# DIO-SMA_Supply.net
KiCad netlist of a schematic drawn in Altium Designer
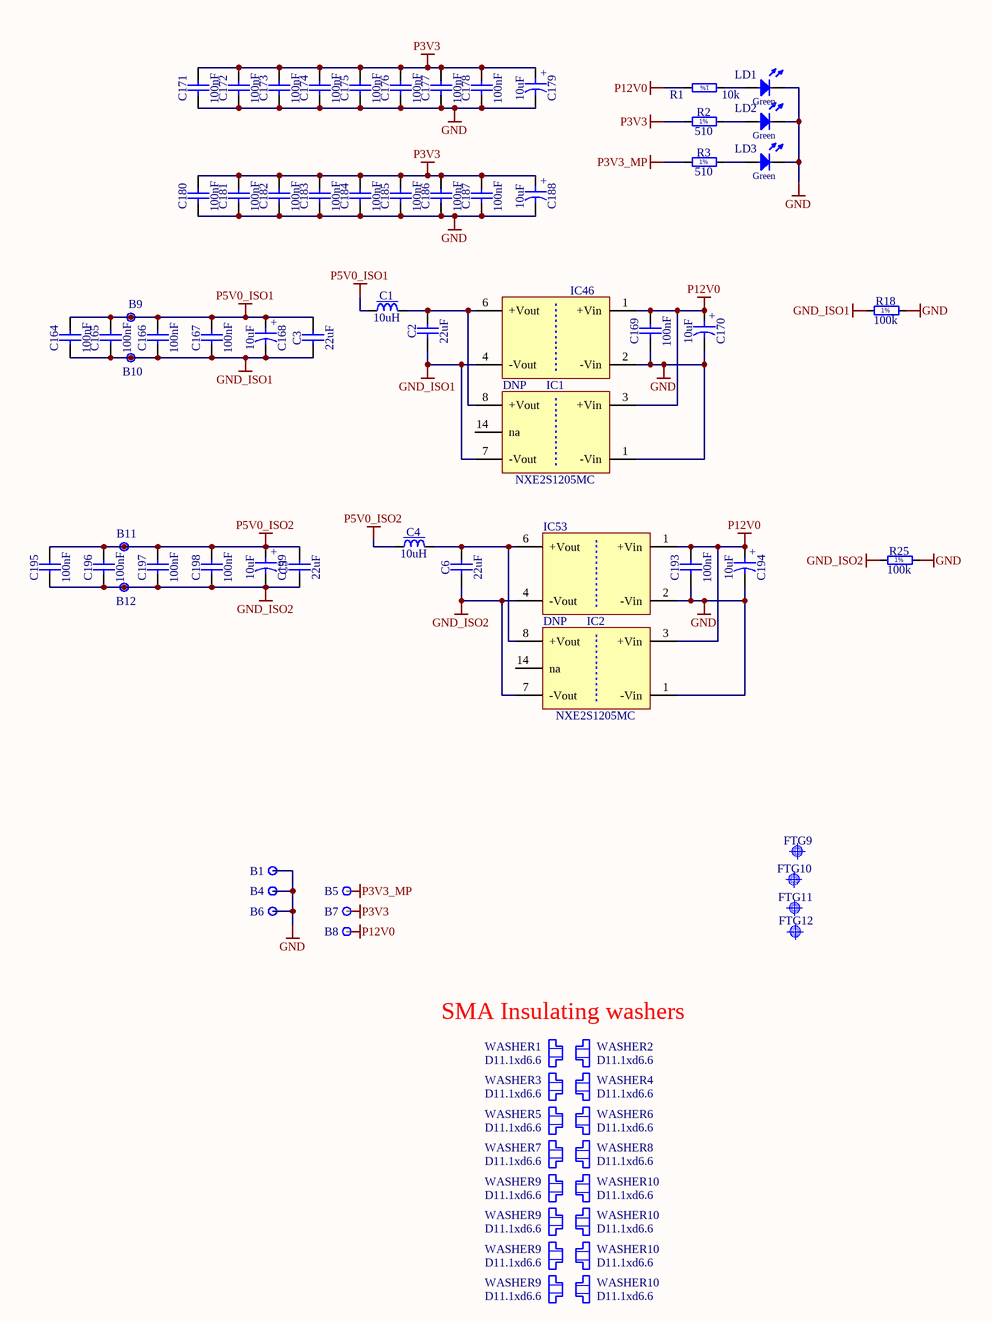
[diagram p0: DIO-SMA_Supply.SchDoc]

(export (version "E")
  (design (tool "Eeschema 10.0.6"))
  (components
    (comp (ref "B1")
      (value "Plated Hole")
      (footprint "c130h60")
      (description "Single Terminal Socket")
      (fields (field (name "PART NUMBER") "PLATED_HOLE0.6_PAD1.3") (field (name "AUTHOR") "CERN DEM MR"))
      (libsource (lib "Eletro-mechanical") (part "Single Terminal Socket"))
    )
    (comp (ref "B4")
      (value "Plated Hole")
      (footprint "c130h60")
      (description "Single Terminal Socket")
      (fields (field (name "PART NUMBER") "PLATED_HOLE0.6_PAD1.3") (field (name "AUTHOR") "CERN DEM MR"))
      (libsource (lib "Eletro-mechanical") (part "Single Terminal Socket"))
    )
    (comp (ref "B5")
      (value "Plated Hole")
      (footprint "c130h60")
      (description "Single Terminal Socket")
      (fields (field (name "PART NUMBER") "PLATED_HOLE0.6_PAD1.3") (field (name "AUTHOR") "CERN DEM MR"))
      (libsource (lib "Eletro-mechanical") (part "Single Terminal Socket"))
    )
    (comp (ref "B6")
      (value "Plated Hole")
      (footprint "c130h60")
      (description "Single Terminal Socket")
      (fields (field (name "PART NUMBER") "PLATED_HOLE0.6_PAD1.3") (field (name "AUTHOR") "CERN DEM MR"))
      (libsource (lib "Eletro-mechanical") (part "Single Terminal Socket"))
    )
    (comp (ref "B7")
      (value "Plated Hole")
      (footprint "c130h60")
      (description "Single Terminal Socket")
      (fields (field (name "PART NUMBER") "PLATED_HOLE0.6_PAD1.3") (field (name "AUTHOR") "CERN DEM MR"))
      (libsource (lib "Eletro-mechanical") (part "Single Terminal Socket"))
    )
    (comp (ref "B8")
      (value "Plated Hole")
      (footprint "c130h60")
      (description "Single Terminal Socket")
      (fields (field (name "PART NUMBER") "PLATED_HOLE0.6_PAD1.3") (field (name "AUTHOR") "CERN DEM MR"))
      (libsource (lib "Eletro-mechanical") (part "Single Terminal Socket"))
    )
    (comp (ref "B9")
      (value "Plated Hole")
      (footprint "c130h60")
      (description "Single Terminal Socket")
      (fields (field (name "PART NUMBER") "PLATED_HOLE0.6_PAD1.3") (field (name "AUTHOR") "CERN DEM MR"))
      (libsource (lib "Eletro-mechanical") (part "Single Terminal Socket"))
    )
    (comp (ref "B10")
      (value "Plated Hole")
      (footprint "c130h60")
      (description "Single Terminal Socket")
      (fields (field (name "PART NUMBER") "PLATED_HOLE0.6_PAD1.3") (field (name "AUTHOR") "CERN DEM MR"))
      (libsource (lib "Eletro-mechanical") (part "Single Terminal Socket"))
    )
    (comp (ref "B11")
      (value "Plated Hole")
      (footprint "c130h60")
      (description "Single Terminal Socket")
      (fields (field (name "PART NUMBER") "PLATED_HOLE0.6_PAD1.3") (field (name "AUTHOR") "CERN DEM MR"))
      (libsource (lib "Eletro-mechanical") (part "Single Terminal Socket"))
    )
    (comp (ref "B12")
      (value "Plated Hole")
      (footprint "c130h60")
      (description "Single Terminal Socket")
      (fields (field (name "PART NUMBER") "PLATED_HOLE0.6_PAD1.3") (field (name "AUTHOR") "CERN DEM MR"))
      (libsource (lib "Eletro-mechanical") (part "Single Terminal Socket"))
    )
    (comp (ref "C1")
      (value "10uH")
      (footprint "IND_MURATA-PS_8400")
      (description "Inductor With Core")
      (fields
        (field (name "PART NUMBER") "IND_10UH_10%_MURATA-PS_8400")
        (field (name "POWER") "950mA")
        (field (name "AUTHOR") "CERN DEM JLC")
      )
      (libsource (lib "Inductors & Transformers") (part "Inductor With Magnetic core"))
    )
    (comp (ref "C2")
      (value "22uF")
      (footprint "CAPC2012X135N")
      (description "Non-polarised capacitor")
      (fields
        (field (name "PART NUMBER") "CC0805_22UF_16V_10%_X5R")
        (field (name "VOLTAGE") "16V")
        (field (name "AUTHOR") "CERN DEM JLC")
      )
      (libsource (lib "Capacitors") (part "Capacitor - non polarized"))
    )
    (comp (ref "C3")
      (value "22uF")
      (footprint "CAPC2012X135N")
      (description "Non-polarised capacitor")
      (fields
        (field (name "PART NUMBER") "CC0805_22UF_16V_10%_X5R")
        (field (name "VOLTAGE") "16V")
        (field (name "AUTHOR") "CERN DEM JLC")
      )
      (libsource (lib "Capacitors") (part "Capacitor - non polarized"))
    )
    (comp (ref "C4")
      (value "10uH")
      (footprint "IND_MURATA-PS_8400")
      (description "Inductor With Core")
      (fields
        (field (name "PART NUMBER") "IND_10UH_10%_MURATA-PS_8400")
        (field (name "POWER") "950mA")
        (field (name "AUTHOR") "CERN DEM JLC")
      )
      (libsource (lib "Inductors & Transformers") (part "Inductor With Magnetic core"))
    )
    (comp (ref "C5")
      (value "22uF")
      (footprint "CAPC2012X135N")
      (description "Non-polarised capacitor")
      (fields
        (field (name "PART NUMBER") "CC0805_22UF_16V_10%_X5R")
        (field (name "VOLTAGE") "16V")
        (field (name "AUTHOR") "CERN DEM JLC")
      )
      (libsource (lib "Capacitors") (part "Capacitor - non polarized"))
    )
    (comp (ref "C6")
      (value "22uF")
      (footprint "CAPC2012X135N")
      (description "Non-polarised capacitor")
      (fields
        (field (name "PART NUMBER") "CC0805_22UF_16V_10%_X5R")
        (field (name "VOLTAGE") "16V")
        (field (name "AUTHOR") "CERN DEM JLC")
      )
      (libsource (lib "Capacitors") (part "Capacitor - non polarized"))
    )
    (comp (ref "C164")
      (value "100nF")
      (footprint "CAPC1005X55N")
      (description "Non-polarised capacitor")
      (fields
        (field (name "PART NUMBER") "CC0402_100NF_16V_10%_X5R")
        (field (name "VOLTAGE") "16V")
        (field (name "AUTHOR") "CERN DEM JLC")
      )
      (libsource (lib "Capacitors") (part "Capacitor - non polarized"))
    )
    (comp (ref "C165")
      (value "100nF")
      (footprint "CAPC1005X55N")
      (description "Non-polarised capacitor")
      (fields
        (field (name "PART NUMBER") "CC0402_100NF_16V_10%_X5R")
        (field (name "VOLTAGE") "16V")
        (field (name "AUTHOR") "CERN DEM JLC")
      )
      (libsource (lib "Capacitors") (part "Capacitor - non polarized"))
    )
    (comp (ref "C166")
      (value "100nF")
      (footprint "CAPC1005X55N")
      (description "Non-polarised capacitor")
      (fields
        (field (name "PART NUMBER") "CC0402_100NF_16V_10%_X5R")
        (field (name "VOLTAGE") "16V")
        (field (name "AUTHOR") "CERN DEM JLC")
      )
      (libsource (lib "Capacitors") (part "Capacitor - non polarized"))
    )
    (comp (ref "C167")
      (value "100nF")
      (footprint "CAPC1005X55N")
      (description "Non-polarised capacitor")
      (fields
        (field (name "PART NUMBER") "CC0402_100NF_16V_10%_X5R")
        (field (name "VOLTAGE") "16V")
        (field (name "AUTHOR") "CERN DEM JLC")
      )
      (libsource (lib "Capacitors") (part "Capacitor - non polarized"))
    )
    (comp (ref "C168")
      (value "10uF")
      (footprint "CAPAE430X540N")
      (description "Polarised capacitor")
      (fields
        (field (name "PART NUMBER") "CAE430-540_10UF_16V_20%")
        (field (name "VOLTAGE") "16V")
        (field (name "AUTHOR") "CERN DEM JLC")
      )
      (libsource (lib "Capacitors") (part "Capacitor - polarized"))
    )
    (comp (ref "C169")
      (value "100nF")
      (footprint "CAPC1005X55N")
      (description "Non-polarised capacitor")
      (fields
        (field (name "PART NUMBER") "CC0402_100NF_16V_10%_X5R")
        (field (name "VOLTAGE") "16V")
        (field (name "AUTHOR") "CERN DEM JLC")
      )
      (libsource (lib "Capacitors") (part "Capacitor - non polarized"))
    )
    (comp (ref "C170")
      (value "10uF")
      (footprint "CAPAE430X540N")
      (description "Polarised capacitor")
      (fields
        (field (name "PART NUMBER") "CAE430-540_10UF_16V_20%")
        (field (name "VOLTAGE") "16V")
        (field (name "AUTHOR") "CERN DEM JLC")
      )
      (libsource (lib "Capacitors") (part "Capacitor - polarized"))
    )
    (comp (ref "C171")
      (value "100nF")
      (footprint "CAPC1005X55N")
      (description "Non-polarised capacitor")
      (fields
        (field (name "PART NUMBER") "CC0402_100NF_16V_10%_X5R")
        (field (name "VOLTAGE") "16V")
        (field (name "AUTHOR") "CERN DEM JLC")
      )
      (libsource (lib "Capacitors") (part "Capacitor - non polarized"))
    )
    (comp (ref "C172")
      (value "100nF")
      (footprint "CAPC1005X55N")
      (description "Non-polarised capacitor")
      (fields
        (field (name "PART NUMBER") "CC0402_100NF_16V_10%_X5R")
        (field (name "VOLTAGE") "16V")
        (field (name "AUTHOR") "CERN DEM JLC")
      )
      (libsource (lib "Capacitors") (part "Capacitor - non polarized"))
    )
    (comp (ref "C173")
      (value "100nF")
      (footprint "CAPC1005X55N")
      (description "Non-polarised capacitor")
      (fields
        (field (name "PART NUMBER") "CC0402_100NF_16V_10%_X5R")
        (field (name "VOLTAGE") "16V")
        (field (name "AUTHOR") "CERN DEM JLC")
      )
      (libsource (lib "Capacitors") (part "Capacitor - non polarized"))
    )
    (comp (ref "C174")
      (value "100nF")
      (footprint "CAPC1005X55N")
      (description "Non-polarised capacitor")
      (fields
        (field (name "PART NUMBER") "CC0402_100NF_16V_10%_X5R")
        (field (name "VOLTAGE") "16V")
        (field (name "AUTHOR") "CERN DEM JLC")
      )
      (libsource (lib "Capacitors") (part "Capacitor - non polarized"))
    )
    (comp (ref "C175")
      (value "100nF")
      (footprint "CAPC1005X55N")
      (description "Non-polarised capacitor")
      (fields
        (field (name "PART NUMBER") "CC0402_100NF_16V_10%_X5R")
        (field (name "VOLTAGE") "16V")
        (field (name "AUTHOR") "CERN DEM JLC")
      )
      (libsource (lib "Capacitors") (part "Capacitor - non polarized"))
    )
    (comp (ref "C176")
      (value "100nF")
      (footprint "CAPC1005X55N")
      (description "Non-polarised capacitor")
      (fields
        (field (name "PART NUMBER") "CC0402_100NF_16V_10%_X5R")
        (field (name "VOLTAGE") "16V")
        (field (name "AUTHOR") "CERN DEM JLC")
      )
      (libsource (lib "Capacitors") (part "Capacitor - non polarized"))
    )
    (comp (ref "C177")
      (value "100nF")
      (footprint "CAPC1005X55N")
      (description "Non-polarised capacitor")
      (fields
        (field (name "PART NUMBER") "CC0402_100NF_16V_10%_X5R")
        (field (name "VOLTAGE") "16V")
        (field (name "AUTHOR") "CERN DEM JLC")
      )
      (libsource (lib "Capacitors") (part "Capacitor - non polarized"))
    )
    (comp (ref "C178")
      (value "100nF")
      (footprint "CAPC1005X55N")
      (description "Non-polarised capacitor")
      (fields
        (field (name "PART NUMBER") "CC0402_100NF_16V_10%_X5R")
        (field (name "VOLTAGE") "16V")
        (field (name "AUTHOR") "CERN DEM JLC")
      )
      (libsource (lib "Capacitors") (part "Capacitor - non polarized"))
    )
    (comp (ref "C179")
      (value "10uF")
      (footprint "CAPAE430X540N")
      (description "Polarised capacitor")
      (fields
        (field (name "PART NUMBER") "CAE430-540_10UF_16V_20%")
        (field (name "VOLTAGE") "16V")
        (field (name "AUTHOR") "CERN DEM JLC")
      )
      (libsource (lib "Capacitors") (part "Capacitor - polarized"))
    )
    (comp (ref "C180")
      (value "100nF")
      (footprint "CAPC1005X55N")
      (description "Non-polarised capacitor")
      (fields
        (field (name "PART NUMBER") "CC0402_100NF_16V_10%_X5R")
        (field (name "VOLTAGE") "16V")
        (field (name "AUTHOR") "CERN DEM JLC")
      )
      (libsource (lib "Capacitors") (part "Capacitor - non polarized"))
    )
    (comp (ref "C181")
      (value "100nF")
      (footprint "CAPC1005X55N")
      (description "Non-polarised capacitor")
      (fields
        (field (name "PART NUMBER") "CC0402_100NF_16V_10%_X5R")
        (field (name "VOLTAGE") "16V")
        (field (name "AUTHOR") "CERN DEM JLC")
      )
      (libsource (lib "Capacitors") (part "Capacitor - non polarized"))
    )
    (comp (ref "C182")
      (value "100nF")
      (footprint "CAPC1005X55N")
      (description "Non-polarised capacitor")
      (fields
        (field (name "PART NUMBER") "CC0402_100NF_16V_10%_X5R")
        (field (name "VOLTAGE") "16V")
        (field (name "AUTHOR") "CERN DEM JLC")
      )
      (libsource (lib "Capacitors") (part "Capacitor - non polarized"))
    )
    (comp (ref "C183")
      (value "100nF")
      (footprint "CAPC1005X55N")
      (description "Non-polarised capacitor")
      (fields
        (field (name "PART NUMBER") "CC0402_100NF_16V_10%_X5R")
        (field (name "VOLTAGE") "16V")
        (field (name "AUTHOR") "CERN DEM JLC")
      )
      (libsource (lib "Capacitors") (part "Capacitor - non polarized"))
    )
    (comp (ref "C184")
      (value "100nF")
      (footprint "CAPC1005X55N")
      (description "Non-polarised capacitor")
      (fields
        (field (name "PART NUMBER") "CC0402_100NF_16V_10%_X5R")
        (field (name "VOLTAGE") "16V")
        (field (name "AUTHOR") "CERN DEM JLC")
      )
      (libsource (lib "Capacitors") (part "Capacitor - non polarized"))
    )
    (comp (ref "C185")
      (value "100nF")
      (footprint "CAPC1005X55N")
      (description "Non-polarised capacitor")
      (fields
        (field (name "PART NUMBER") "CC0402_100NF_16V_10%_X5R")
        (field (name "VOLTAGE") "16V")
        (field (name "AUTHOR") "CERN DEM JLC")
      )
      (libsource (lib "Capacitors") (part "Capacitor - non polarized"))
    )
    (comp (ref "C186")
      (value "100nF")
      (footprint "CAPC1005X55N")
      (description "Non-polarised capacitor")
      (fields
        (field (name "PART NUMBER") "CC0402_100NF_16V_10%_X5R")
        (field (name "VOLTAGE") "16V")
        (field (name "AUTHOR") "CERN DEM JLC")
      )
      (libsource (lib "Capacitors") (part "Capacitor - non polarized"))
    )
    (comp (ref "C187")
      (value "100nF")
      (footprint "CAPC1005X55N")
      (description "Non-polarised capacitor")
      (fields
        (field (name "PART NUMBER") "CC0402_100NF_16V_10%_X5R")
        (field (name "VOLTAGE") "16V")
        (field (name "AUTHOR") "CERN DEM JLC")
      )
      (libsource (lib "Capacitors") (part "Capacitor - non polarized"))
    )
    (comp (ref "C188")
      (value "10uF")
      (footprint "CAPAE430X540N")
      (description "Polarised capacitor")
      (fields
        (field (name "PART NUMBER") "CAE430-540_10UF_16V_20%")
        (field (name "VOLTAGE") "16V")
        (field (name "AUTHOR") "CERN DEM JLC")
      )
      (libsource (lib "Capacitors") (part "Capacitor - polarized"))
    )
    (comp (ref "C193")
      (value "100nF")
      (footprint "CAPC1005X55N")
      (description "Non-polarised capacitor")
      (fields
        (field (name "PART NUMBER") "CC0402_100NF_16V_10%_X5R")
        (field (name "VOLTAGE") "16V")
        (field (name "AUTHOR") "CERN DEM JLC")
      )
      (libsource (lib "Capacitors") (part "Capacitor - non polarized"))
    )
    (comp (ref "C194")
      (value "10uF")
      (footprint "CAPAE430X540N")
      (description "Polarised capacitor")
      (fields
        (field (name "PART NUMBER") "CAE430-540_10UF_16V_20%")
        (field (name "VOLTAGE") "16V")
        (field (name "AUTHOR") "CERN DEM JLC")
      )
      (libsource (lib "Capacitors") (part "Capacitor - polarized"))
    )
    (comp (ref "C195")
      (value "100nF")
      (footprint "CAPC1005X55N")
      (description "Non-polarised capacitor")
      (fields
        (field (name "PART NUMBER") "CC0402_100NF_16V_10%_X5R")
        (field (name "VOLTAGE") "16V")
        (field (name "AUTHOR") "CERN DEM JLC")
      )
      (libsource (lib "Capacitors") (part "Capacitor - non polarized"))
    )
    (comp (ref "C196")
      (value "100nF")
      (footprint "CAPC1005X55N")
      (description "Non-polarised capacitor")
      (fields
        (field (name "PART NUMBER") "CC0402_100NF_16V_10%_X5R")
        (field (name "VOLTAGE") "16V")
        (field (name "AUTHOR") "CERN DEM JLC")
      )
      (libsource (lib "Capacitors") (part "Capacitor - non polarized"))
    )
    (comp (ref "C197")
      (value "100nF")
      (footprint "CAPC1005X55N")
      (description "Non-polarised capacitor")
      (fields
        (field (name "PART NUMBER") "CC0402_100NF_16V_10%_X5R")
        (field (name "VOLTAGE") "16V")
        (field (name "AUTHOR") "CERN DEM JLC")
      )
      (libsource (lib "Capacitors") (part "Capacitor - non polarized"))
    )
    (comp (ref "C198")
      (value "100nF")
      (footprint "CAPC1005X55N")
      (description "Non-polarised capacitor")
      (fields
        (field (name "PART NUMBER") "CC0402_100NF_16V_10%_X5R")
        (field (name "VOLTAGE") "16V")
        (field (name "AUTHOR") "CERN DEM JLC")
      )
      (libsource (lib "Capacitors") (part "Capacitor - non polarized"))
    )
    (comp (ref "C199")
      (value "10uF")
      (footprint "CAPAE430X540N")
      (description "Polarised capacitor")
      (fields
        (field (name "PART NUMBER") "CAE430-540_10UF_16V_20%")
        (field (name "VOLTAGE") "16V")
        (field (name "AUTHOR") "CERN DEM JLC")
      )
      (libsource (lib "Capacitors") (part "Capacitor - polarized"))
    )
    (comp (ref "FTG9")
      (value "Use only in PCB")
      (footprint "FIDUCIAL_TOP_C100-200")
      (description "Fiducial Target")
      (fields (field (name "PART NUMBER") "FIDUCIAL_TARGET_C100-200") (field (name "AUTHOR") "CERN DEM JLC"))
      (libsource (lib "Eletro-mechanical") (part "Fiducial Target"))
    )
    (comp (ref "FTG10")
      (value "Use only in PCB")
      (footprint "FIDUCIAL_TOP_S100-200")
      (description "Fiducial Target")
      (fields (field (name "PART NUMBER") "FIDUCIAL_TARGET_S100-200") (field (name "AUTHOR") "CERN DEM JLC"))
      (libsource (lib "Eletro-mechanical") (part "Fiducial Target"))
    )
    (comp (ref "FTG11")
      (value "Use only in PCB")
      (footprint "FIDUCIAL_TOP_S200-400")
      (description "Fiducial Target")
      (fields (field (name "PART NUMBER") "FIDUCIAL_TARGET_S200-400") (field (name "AUTHOR") "CERN DEM JLC"))
      (libsource (lib "Eletro-mechanical") (part "Fiducial Target"))
    )
    (comp (ref "FTG12")
      (value "Use only in PCB")
      (footprint "FIDUCIAL_TOP_S100-200")
      (description "Fiducial Target")
      (fields (field (name "PART NUMBER") "FIDUCIAL_TARGET_S100-200") (field (name "AUTHOR") "CERN DEM JLC"))
      (libsource (lib "Eletro-mechanical") (part "Fiducial Target"))
    )
    (comp (ref "IC1")
      (value "NXE2S1205MC")
      (footprint "DCDC_MURATA_NXE2")
      (description "MURATA, NXE2 Serie, Dual Output DCDC Converter")
      (fields (field (name "MANUFACTURER") "MURATA POWER SOLUTIONS") (field (name "AUTHOR") "CERN DEM MR"))
      (libsource (lib "LIBRARY_SCH") (part "DCDC_MURATA_NXE2S1205MC"))
    )
    (comp (ref "IC2")
      (value "NXE2S1205MC")
      (footprint "DCDC_MURATA_NXE2")
      (description "MURATA, NXE2 Serie, Dual Output DCDC Converter")
      (fields (field (name "MANUFACTURER") "MURATA POWER SOLUTIONS") (field (name "AUTHOR") "CERN DEM MR"))
      (libsource (lib "LIBRARY_SCH") (part "DCDC_MURATA_NXE2S1205MC"))
    )
    (comp (ref "IC46")
      (value "DNP")
      (footprint "DCDC_TRACO_TMA")
      (description "1 W Watt, 10.8-13.2VDCVin, 5 V@0.2 A")
      (fields
        (field (name "PART NUMBER") "TMA 1205S")
        (field (name "MANUFACTURER") "TRACO POWER")
        (field (name "AUTHOR") "GK")
      )
      (libsource (lib "LIBRARY_SCH") (part "DC/DC_TRACO_TMA1205S"))
    )
    (comp (ref "IC53")
      (value "DNP")
      (footprint "DCDC_TRACO_TMA")
      (description "1 W Watt, 10.8-13.2VDCVin, 5 V@0.2 A")
      (fields
        (field (name "PART NUMBER") "TMA 1205S")
        (field (name "MANUFACTURER") "TRACO POWER")
        (field (name "AUTHOR") "GK")
      )
      (libsource (lib "LIBRARY_SCH") (part "DC/DC_TRACO_TMA1205S"))
    )
    (comp (ref "LD1")
      (value "Green")
      (footprint "LED_KINGBRIGHT_KPH-1608CGCK")
      (description "LED Green 1C 2A")
      (fields
        (field (name "PART NUMBER") "LED_KINGBRIGHT_KPH-1608CGCK")
        (field (name "MANUFACTURER") "KINGBRIGHT")
        (field (name "AUTHOR") "CERN DEM JLC")
      )
      (libsource (lib "ICs And Semiconductors") (part "LED Green 1C 2A"))
    )
    (comp (ref "LD2")
      (value "Green")
      (footprint "LED_KINGBRIGHT_KPH-1608CGCK")
      (description "LED Green 1C 2A")
      (fields
        (field (name "PART NUMBER") "LED_KINGBRIGHT_KPH-1608CGCK")
        (field (name "MANUFACTURER") "KINGBRIGHT")
        (field (name "AUTHOR") "CERN DEM JLC")
      )
      (libsource (lib "ICs And Semiconductors") (part "LED Green 1C 2A"))
    )
    (comp (ref "LD3")
      (value "Green")
      (footprint "LED_KINGBRIGHT_KPH-1608CGCK")
      (description "LED Green 1C 2A")
      (fields
        (field (name "PART NUMBER") "LED_KINGBRIGHT_KPH-1608CGCK")
        (field (name "MANUFACTURER") "KINGBRIGHT")
        (field (name "AUTHOR") "CERN DEM JLC")
      )
      (libsource (lib "ICs And Semiconductors") (part "LED Green 1C 2A"))
    )
    (comp (ref "R1")
      (value "10k")
      (footprint "RESC1005X40N")
      (description "Resistor - 1%")
      (fields
        (field (name "PART NUMBER") "R0402_10K_1%_0.0625W_100PPM")
        (field (name "POWER") "0.0625W")
        (field (name "AUTHOR") "CERN DEM JLC")
      )
      (libsource (lib "Resistors") (part "Resistor - 1%"))
    )
    (comp (ref "R2")
      (value "510")
      (footprint "RESC1005X40N")
      (description "Resistor - 1%")
      (fields
        (field (name "PART NUMBER") "R0402_510R_1%_0.0625W_100PPM")
        (field (name "POWER") "0.0625W")
        (field (name "AUTHOR") "CERN DEM JLC")
      )
      (libsource (lib "Resistors") (part "Resistor - 1%"))
    )
    (comp (ref "R3")
      (value "510")
      (footprint "RESC1005X40N")
      (description "Resistor - 1%")
      (fields
        (field (name "PART NUMBER") "R0402_510R_1%_0.0625W_100PPM")
        (field (name "POWER") "0.0625W")
        (field (name "AUTHOR") "CERN DEM JLC")
      )
      (libsource (lib "Resistors") (part "Resistor - 1%"))
    )
    (comp (ref "R18")
      (value "100k")
      (footprint "RESC2012X60N")
      (description "Resistor - 1%")
      (fields
        (field (name "PART NUMBER") "R0805_100K_1%_0.125W_100PPM")
        (field (name "POWER") "0.125W")
        (field (name "AUTHOR") "CERN DEM JLC")
      )
      (libsource (lib "Resistors") (part "Resistor - 1%"))
    )
    (comp (ref "R25")
      (value "100k")
      (footprint "RESC2012X60N")
      (description "Resistor - 1%")
      (fields
        (field (name "PART NUMBER") "R0805_100K_1%_0.125W_100PPM")
        (field (name "POWER") "0.125W")
        (field (name "AUTHOR") "CERN DEM JLC")
      )
      (libsource (lib "Resistors") (part "Resistor - 1%"))
    )
    (comp (ref "WASHER1")
      (value "D11.1xd6.6")
      (footprint "Keystone_7687")
      (description "SMA_Shoulder Washer")
      (fields
        (field (name "PART NUMBER") "Keystone 7687")
        (field (name "MANUFACTURER") "Keystone")
        (field (name "AUTHOR") "GK")
      )
      (libsource (lib "LIBRARY_SCH") (part "Keystone_7687"))
    )
    (comp (ref "WASHER2")
      (value "D11.1xd6.6")
      (footprint "Keystone_7687")
      (description "SMA_Shoulder Washer")
      (fields
        (field (name "PART NUMBER") "Keystone 7687")
        (field (name "MANUFACTURER") "Keystone")
        (field (name "AUTHOR") "GK")
      )
      (libsource (lib "LIBRARY_SCH") (part "Keystone_7687"))
    )
    (comp (ref "WASHER3")
      (value "D11.1xd6.6")
      (footprint "Keystone_7687")
      (description "SMA_Shoulder Washer")
      (fields
        (field (name "PART NUMBER") "Keystone 7687")
        (field (name "MANUFACTURER") "Keystone")
        (field (name "AUTHOR") "GK")
      )
      (libsource (lib "LIBRARY_SCH") (part "Keystone_7687"))
    )
    (comp (ref "WASHER4")
      (value "D11.1xd6.6")
      (footprint "Keystone_7687")
      (description "SMA_Shoulder Washer")
      (fields
        (field (name "PART NUMBER") "Keystone 7687")
        (field (name "MANUFACTURER") "Keystone")
        (field (name "AUTHOR") "GK")
      )
      (libsource (lib "LIBRARY_SCH") (part "Keystone_7687"))
    )
    (comp (ref "WASHER5")
      (value "D11.1xd6.6")
      (footprint "Keystone_7687")
      (description "SMA_Shoulder Washer")
      (fields
        (field (name "PART NUMBER") "Keystone 7687")
        (field (name "MANUFACTURER") "Keystone")
        (field (name "AUTHOR") "GK")
      )
      (libsource (lib "LIBRARY_SCH") (part "Keystone_7687"))
    )
    (comp (ref "WASHER6")
      (value "D11.1xd6.6")
      (footprint "Keystone_7687")
      (description "SMA_Shoulder Washer")
      (fields
        (field (name "PART NUMBER") "Keystone 7687")
        (field (name "MANUFACTURER") "Keystone")
        (field (name "AUTHOR") "GK")
      )
      (libsource (lib "LIBRARY_SCH") (part "Keystone_7687"))
    )
    (comp (ref "WASHER7")
      (value "D11.1xd6.6")
      (footprint "Keystone_7687")
      (description "SMA_Shoulder Washer")
      (fields
        (field (name "PART NUMBER") "Keystone 7687")
        (field (name "MANUFACTURER") "Keystone")
        (field (name "AUTHOR") "GK")
      )
      (libsource (lib "LIBRARY_SCH") (part "Keystone_7687"))
    )
    (comp (ref "WASHER8")
      (value "D11.1xd6.6")
      (footprint "Keystone_7687")
      (description "SMA_Shoulder Washer")
      (fields
        (field (name "PART NUMBER") "Keystone 7687")
        (field (name "MANUFACTURER") "Keystone")
        (field (name "AUTHOR") "GK")
      )
      (libsource (lib "LIBRARY_SCH") (part "Keystone_7687"))
    )
  )
  (nets
    (net (code "1") (name "GND") (class "Default")
      (node (ref "B1") (pin "1") (pinfunction "1_1") (pintype "bidirectional"))
      (node (ref "B4") (pin "1") (pinfunction "1_1") (pintype "bidirectional"))
      (node (ref "B6") (pin "1") (pinfunction "1_1") (pintype "bidirectional"))
      (node (ref "C169") (pin "1") (pinfunction "1_1") (pintype "passive"))
      (node (ref "C170") (pin "2") (pinfunction "2_2") (pintype "passive"))
      (node (ref "C171") (pin "1") (pinfunction "1_1") (pintype "passive"))
      (node (ref "C172") (pin "1") (pinfunction "1_1") (pintype "passive"))
      (node (ref "C173") (pin "1") (pinfunction "1_1") (pintype "passive"))
      (node (ref "C174") (pin "1") (pinfunction "1_1") (pintype "passive"))
      (node (ref "C175") (pin "1") (pinfunction "1_1") (pintype "passive"))
      (node (ref "C176") (pin "1") (pinfunction "1_1") (pintype "passive"))
      (node (ref "C177") (pin "1") (pinfunction "1_1") (pintype "passive"))
      (node (ref "C178") (pin "1") (pinfunction "1_1") (pintype "passive"))
      (node (ref "C179") (pin "2") (pinfunction "2_2") (pintype "passive"))
      (node (ref "C180") (pin "1") (pinfunction "1_1") (pintype "passive"))
      (node (ref "C181") (pin "1") (pinfunction "1_1") (pintype "passive"))
      (node (ref "C182") (pin "1") (pinfunction "1_1") (pintype "passive"))
      (node (ref "C183") (pin "1") (pinfunction "1_1") (pintype "passive"))
      (node (ref "C184") (pin "1") (pinfunction "1_1") (pintype "passive"))
      (node (ref "C185") (pin "1") (pinfunction "1_1") (pintype "passive"))
      (node (ref "C186") (pin "1") (pinfunction "1_1") (pintype "passive"))
      (node (ref "C187") (pin "1") (pinfunction "1_1") (pintype "passive"))
      (node (ref "C188") (pin "2") (pinfunction "2_2") (pintype "passive"))
      (node (ref "C193") (pin "1") (pinfunction "1_1") (pintype "passive"))
      (node (ref "C194") (pin "2") (pinfunction "2_2") (pintype "passive"))
      (node (ref "IC1") (pin "1") (pinfunction "-Vin_1") (pintype "power_in"))
      (node (ref "IC2") (pin "1") (pinfunction "-Vin_1") (pintype "power_in"))
      (node (ref "IC46") (pin "2") (pinfunction "-Vin_2") (pintype "power_in"))
      (node (ref "IC53") (pin "2") (pinfunction "-Vin_2") (pintype "power_in"))
      (node (ref "LD1") (pin "1") (pinfunction "C_1") (pintype "passive"))
      (node (ref "LD2") (pin "1") (pinfunction "C_1") (pintype "passive"))
      (node (ref "LD3") (pin "1") (pinfunction "C_1") (pintype "passive"))
      (node (ref "R18") (pin "2") (pinfunction "2_2") (pintype "passive"))
      (node (ref "R25") (pin "2") (pinfunction "2_2") (pintype "passive"))
    )
    (net (code "2") (name "GND_ISO1") (class "Default")
      (node (ref "B10") (pin "1") (pinfunction "1_1") (pintype "bidirectional"))
      (node (ref "C164") (pin "1") (pinfunction "1_1") (pintype "passive"))
      (node (ref "C165") (pin "1") (pinfunction "1_1") (pintype "passive"))
      (node (ref "C166") (pin "1") (pinfunction "1_1") (pintype "passive"))
      (node (ref "C167") (pin "1") (pinfunction "1_1") (pintype "passive"))
      (node (ref "C168") (pin "2") (pinfunction "2_2") (pintype "passive"))
      (node (ref "C2") (pin "1") (pinfunction "1_1") (pintype "passive"))
      (node (ref "C3") (pin "1") (pinfunction "1_1") (pintype "passive"))
      (node (ref "IC1") (pin "7") (pinfunction "-Vout_7") (pintype "power_in"))
      (node (ref "IC46") (pin "4") (pinfunction "-Vout_4") (pintype "power_in"))
      (node (ref "R18") (pin "1") (pinfunction "1_1") (pintype "passive"))
    )
    (net (code "3") (name "GND_ISO2") (class "Default")
      (node (ref "B12") (pin "1") (pinfunction "1_1") (pintype "bidirectional"))
      (node (ref "C195") (pin "1") (pinfunction "1_1") (pintype "passive"))
      (node (ref "C196") (pin "1") (pinfunction "1_1") (pintype "passive"))
      (node (ref "C197") (pin "1") (pinfunction "1_1") (pintype "passive"))
      (node (ref "C198") (pin "1") (pinfunction "1_1") (pintype "passive"))
      (node (ref "C199") (pin "2") (pinfunction "2_2") (pintype "passive"))
      (node (ref "C5") (pin "1") (pinfunction "1_1") (pintype "passive"))
      (node (ref "C6") (pin "1") (pinfunction "1_1") (pintype "passive"))
      (node (ref "IC2") (pin "7") (pinfunction "-Vout_7") (pintype "power_in"))
      (node (ref "IC53") (pin "4") (pinfunction "-Vout_4") (pintype "power_in"))
      (node (ref "R25") (pin "1") (pinfunction "1_1") (pintype "passive"))
    )
    (net (code "4") (name "Net-(IC1-+Vout)") (class "Default")
      (node (ref "C1") (pin "2") (pinfunction "2_2") (pintype "passive"))
      (node (ref "C2") (pin "2") (pinfunction "2_2") (pintype "passive"))
      (node (ref "IC1") (pin "8") (pinfunction "+Vout_8") (pintype "power_in"))
      (node (ref "IC46") (pin "6") (pinfunction "+Vout_6") (pintype "power_in"))
    )
    (net (code "5") (name "Net-(IC2-+Vout)") (class "Default")
      (node (ref "C4") (pin "2") (pinfunction "2_2") (pintype "passive"))
      (node (ref "C6") (pin "2") (pinfunction "2_2") (pintype "passive"))
      (node (ref "IC2") (pin "8") (pinfunction "+Vout_8") (pintype "power_in"))
      (node (ref "IC53") (pin "6") (pinfunction "+Vout_6") (pintype "power_in"))
    )
    (net (code "6") (name "Net-(LD1-A)") (class "Default")
      (node (ref "LD1") (pin "2") (pinfunction "A_2") (pintype "passive"))
      (node (ref "R1") (pin "1") (pinfunction "1_1") (pintype "passive"))
    )
    (net (code "7") (name "Net-(LD2-A)") (class "Default")
      (node (ref "LD2") (pin "2") (pinfunction "A_2") (pintype "passive"))
      (node (ref "R2") (pin "2") (pinfunction "2_2") (pintype "passive"))
    )
    (net (code "8") (name "Net-(LD3-A)") (class "Default")
      (node (ref "LD3") (pin "2") (pinfunction "A_2") (pintype "passive"))
      (node (ref "R3") (pin "2") (pinfunction "2_2") (pintype "passive"))
    )
    (net (code "9") (name "P3V3") (class "Default")
      (node (ref "B7") (pin "1") (pinfunction "1_1") (pintype "bidirectional"))
      (node (ref "C171") (pin "2") (pinfunction "2_2") (pintype "passive"))
      (node (ref "C172") (pin "2") (pinfunction "2_2") (pintype "passive"))
      (node (ref "C173") (pin "2") (pinfunction "2_2") (pintype "passive"))
      (node (ref "C174") (pin "2") (pinfunction "2_2") (pintype "passive"))
      (node (ref "C175") (pin "2") (pinfunction "2_2") (pintype "passive"))
      (node (ref "C176") (pin "2") (pinfunction "2_2") (pintype "passive"))
      (node (ref "C177") (pin "2") (pinfunction "2_2") (pintype "passive"))
      (node (ref "C178") (pin "2") (pinfunction "2_2") (pintype "passive"))
      (node (ref "C179") (pin "1") (pinfunction "1_1") (pintype "passive"))
      (node (ref "C180") (pin "2") (pinfunction "2_2") (pintype "passive"))
      (node (ref "C181") (pin "2") (pinfunction "2_2") (pintype "passive"))
      (node (ref "C182") (pin "2") (pinfunction "2_2") (pintype "passive"))
      (node (ref "C183") (pin "2") (pinfunction "2_2") (pintype "passive"))
      (node (ref "C184") (pin "2") (pinfunction "2_2") (pintype "passive"))
      (node (ref "C185") (pin "2") (pinfunction "2_2") (pintype "passive"))
      (node (ref "C186") (pin "2") (pinfunction "2_2") (pintype "passive"))
      (node (ref "C187") (pin "2") (pinfunction "2_2") (pintype "passive"))
      (node (ref "C188") (pin "1") (pinfunction "1_1") (pintype "passive"))
      (node (ref "R2") (pin "1") (pinfunction "1_1") (pintype "passive"))
    )
    (net (code "10") (name "P3V3_MP") (class "Default")
      (node (ref "B5") (pin "1") (pinfunction "1_1") (pintype "bidirectional"))
      (node (ref "R3") (pin "1") (pinfunction "1_1") (pintype "passive"))
    )
    (net (code "11") (name "P5V0_ISO1") (class "Default")
      (node (ref "B9") (pin "1") (pinfunction "1_1") (pintype "bidirectional"))
      (node (ref "C1") (pin "1") (pinfunction "1_1") (pintype "passive"))
      (node (ref "C164") (pin "2") (pinfunction "2_2") (pintype "passive"))
      (node (ref "C165") (pin "2") (pinfunction "2_2") (pintype "passive"))
      (node (ref "C166") (pin "2") (pinfunction "2_2") (pintype "passive"))
      (node (ref "C167") (pin "2") (pinfunction "2_2") (pintype "passive"))
      (node (ref "C168") (pin "1") (pinfunction "1_1") (pintype "passive"))
      (node (ref "C3") (pin "2") (pinfunction "2_2") (pintype "passive"))
    )
    (net (code "12") (name "P5V0_ISO2") (class "Default")
      (node (ref "B11") (pin "1") (pinfunction "1_1") (pintype "bidirectional"))
      (node (ref "C195") (pin "2") (pinfunction "2_2") (pintype "passive"))
      (node (ref "C196") (pin "2") (pinfunction "2_2") (pintype "passive"))
      (node (ref "C197") (pin "2") (pinfunction "2_2") (pintype "passive"))
      (node (ref "C198") (pin "2") (pinfunction "2_2") (pintype "passive"))
      (node (ref "C199") (pin "1") (pinfunction "1_1") (pintype "passive"))
      (node (ref "C4") (pin "1") (pinfunction "1_1") (pintype "passive"))
      (node (ref "C5") (pin "2") (pinfunction "2_2") (pintype "passive"))
    )
    (net (code "13") (name "P12V0") (class "Default")
      (node (ref "B8") (pin "1") (pinfunction "1_1") (pintype "bidirectional"))
      (node (ref "C169") (pin "2") (pinfunction "2_2") (pintype "passive"))
      (node (ref "C170") (pin "1") (pinfunction "1_1") (pintype "passive"))
      (node (ref "C193") (pin "2") (pinfunction "2_2") (pintype "passive"))
      (node (ref "C194") (pin "1") (pinfunction "1_1") (pintype "passive"))
      (node (ref "IC1") (pin "3") (pinfunction "+Vin_3") (pintype "power_in"))
      (node (ref "IC2") (pin "3") (pinfunction "+Vin_3") (pintype "power_in"))
      (node (ref "IC46") (pin "1") (pinfunction "+Vin_1") (pintype "power_in"))
      (node (ref "IC53") (pin "1") (pinfunction "+Vin_1") (pintype "power_in"))
      (node (ref "R1") (pin "2") (pinfunction "2_2") (pintype "passive"))
    )
    (net (code "14") (name "unconnected-(IC1-na-Pad14)") (class "Default")
      (node (ref "IC1") (pin "14") (pinfunction "na_14") (pintype "passive"))
    )
    (net (code "15") (name "unconnected-(IC2-na-Pad14)") (class "Default")
      (node (ref "IC2") (pin "14") (pinfunction "na_14") (pintype "passive"))
    )
  )
)
